# Digital_Isolation.net
KiCad netlist of a schematic drawn in Altium Designer
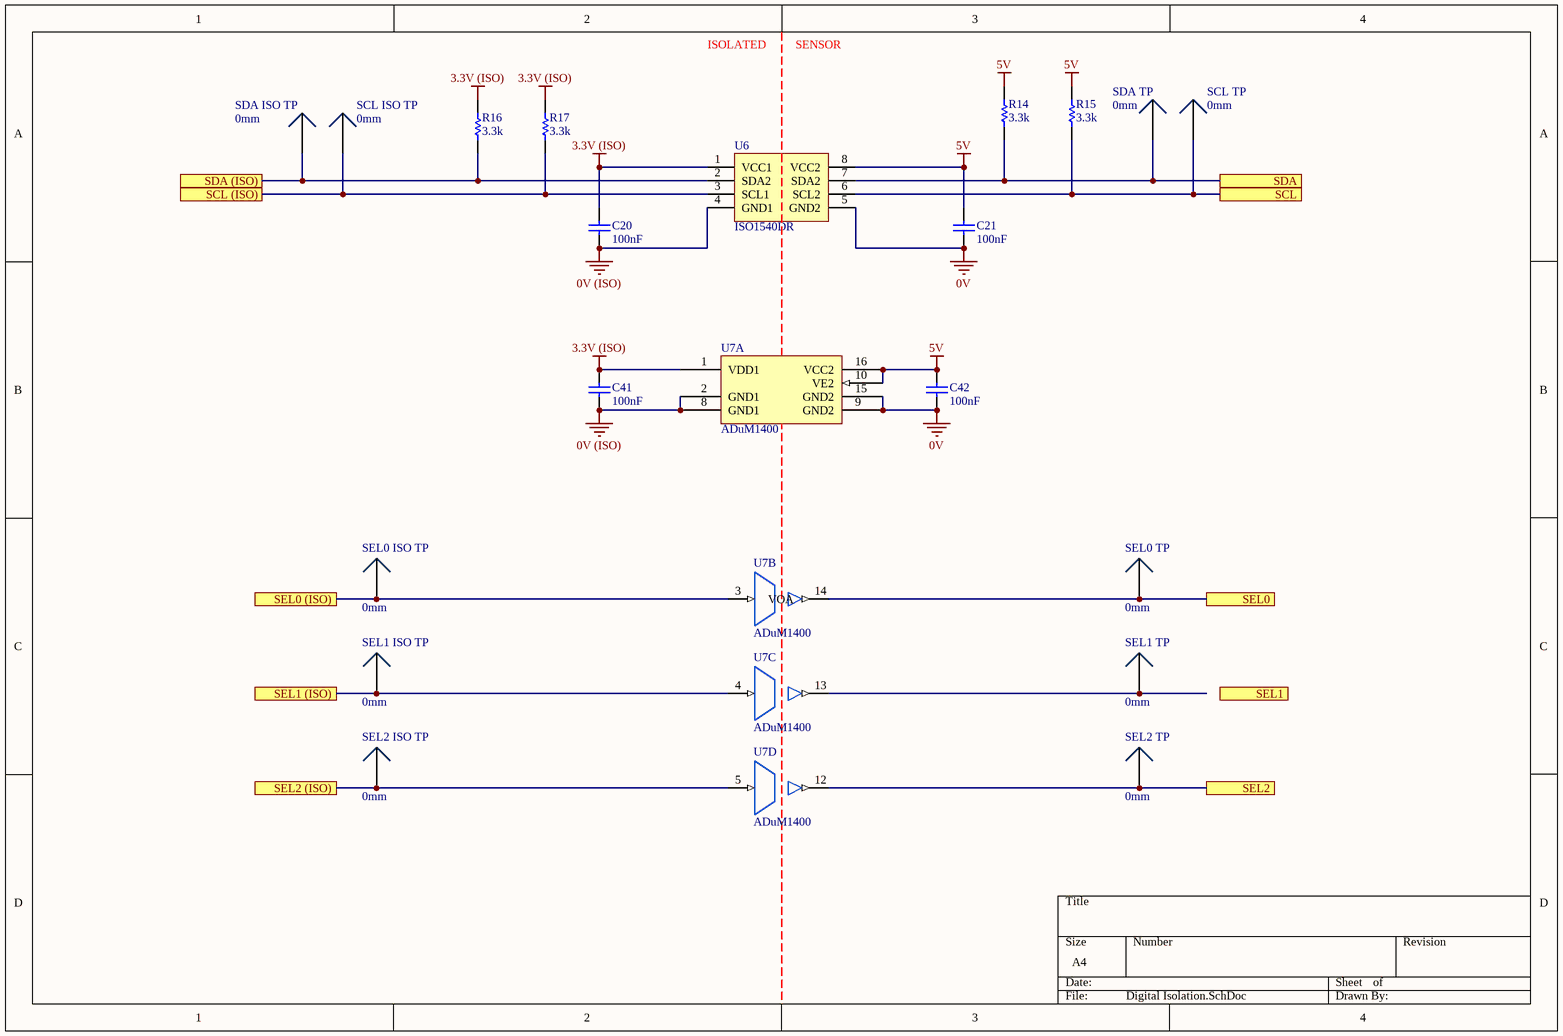
[diagram p0: Digital Isolation.SchDoc]

(export (version "E")
  (design (tool "Eeschema 10.0.6"))
  (components
    (comp (ref "C20")
      (value "100nF")
      (footprint "0805")
      (fields
        (field (name "PART NUMBER") "GCM21BR71E104KA37L")
        (field (name "TOLERANCE") "10%")
        (field (name "MANUFACTURER") "muRata")
      )
      (libsource (lib "ts_20-standard-library") (part "Capacitor"))
    )
    (comp (ref "C21")
      (value "100nF")
      (footprint "0805")
      (fields
        (field (name "PART NUMBER") "GCM21BR71E104KA37L")
        (field (name "TOLERANCE") "10%")
        (field (name "MANUFACTURER") "muRata")
      )
      (libsource (lib "ts_20-standard-library") (part "Capacitor"))
    )
    (comp (ref "C41")
      (value "100nF")
      (footprint "0805")
      (fields
        (field (name "PART NUMBER") "GCM21BR71H104KA37L")
        (field (name "TOLERANCE") "±10%")
        (field (name "MANUFACTURER") "muRata")
      )
      (libsource (lib "ts_20-standard-library") (part "Capacitor"))
    )
    (comp (ref "C42")
      (value "100nF")
      (footprint "0805")
      (fields
        (field (name "PART NUMBER") "GCM21BR71H104KA37L")
        (field (name "TOLERANCE") "±10%")
        (field (name "MANUFACTURER") "muRata")
      )
      (libsource (lib "ts_20-standard-library") (part "Capacitor"))
    )
    (comp (ref "R14")
      (value "3.3k")
      (footprint "0805")
      (fields
        (field (name "PART NUMBER") "RC0805FR073K3L")
        (field (name "MANUFACTURER") "YAGEO")
        (field (name "TOLERANCE") "0.01")
      )
      (libsource (lib "ts_20-standard-library") (part "Resistor"))
    )
    (comp (ref "R15")
      (value "3.3k")
      (footprint "0805")
      (fields
        (field (name "PART NUMBER") "RC0805FR073K3L")
        (field (name "MANUFACTURER") "YAGEO")
        (field (name "TOLERANCE") "0.01")
      )
      (libsource (lib "ts_20-standard-library") (part "Resistor"))
    )
    (comp (ref "R16")
      (value "3.3k")
      (footprint "0805")
      (fields
        (field (name "PART NUMBER") "RC0805FR073K3L")
        (field (name "MANUFACTURER") "YAGEO")
        (field (name "TOLERANCE") "0.01")
      )
      (libsource (lib "ts_20-standard-library") (part "Resistor"))
    )
    (comp (ref "R17")
      (value "3.3k")
      (footprint "0805")
      (fields
        (field (name "PART NUMBER") "RC0805FR073K3L")
        (field (name "MANUFACTURER") "YAGEO")
        (field (name "TOLERANCE") "0.01")
      )
      (libsource (lib "ts_20-standard-library") (part "Resistor"))
    )
    (comp (ref "SCL ISO TP")
      (value "0mm")
      (footprint "SMD Test Point")
      (fields (field (name "PART NUMBER") "SMD Test Point") (field (name "CONTACT") "NA"))
      (libsource (lib "ts_20-standard-connectors") (part "Test Point"))
    )
    (comp (ref "SCL TP")
      (value "0mm")
      (footprint "SMD Test Point")
      (fields (field (name "PART NUMBER") "SMD Test Point") (field (name "CONTACT") "NA"))
      (libsource (lib "ts_20-standard-connectors") (part "Test Point"))
    )
    (comp (ref "SDA ISO TP")
      (value "0mm")
      (footprint "SMD Test Point")
      (fields (field (name "PART NUMBER") "SMD Test Point") (field (name "CONTACT") "NA"))
      (libsource (lib "ts_20-standard-connectors") (part "Test Point"))
    )
    (comp (ref "SDA TP")
      (value "0mm")
      (footprint "SMD Test Point")
      (fields (field (name "PART NUMBER") "SMD Test Point") (field (name "CONTACT") "NA"))
      (libsource (lib "ts_20-standard-connectors") (part "Test Point"))
    )
    (comp (ref "SEL0 ISO TP")
      (value "0mm")
      (footprint "SMD Test Point")
      (fields (field (name "PART NUMBER") "SMD Test Point") (field (name "CONTACT") "NA"))
      (libsource (lib "ts_20-standard-connectors") (part "Test Point"))
    )
    (comp (ref "SEL0 TP")
      (value "0mm")
      (footprint "SMD Test Point")
      (fields (field (name "PART NUMBER") "SMD Test Point") (field (name "CONTACT") "NA"))
      (libsource (lib "ts_20-standard-connectors") (part "Test Point"))
    )
    (comp (ref "SEL1 ISO TP")
      (value "0mm")
      (footprint "SMD Test Point")
      (fields (field (name "PART NUMBER") "SMD Test Point") (field (name "CONTACT") "NA"))
      (libsource (lib "ts_20-standard-connectors") (part "Test Point"))
    )
    (comp (ref "SEL1 TP")
      (value "0mm")
      (footprint "SMD Test Point")
      (fields (field (name "PART NUMBER") "SMD Test Point") (field (name "CONTACT") "NA"))
      (libsource (lib "ts_20-standard-connectors") (part "Test Point"))
    )
    (comp (ref "SEL2 ISO TP")
      (value "0mm")
      (footprint "SMD Test Point")
      (fields (field (name "PART NUMBER") "SMD Test Point") (field (name "CONTACT") "NA"))
      (libsource (lib "ts_20-standard-connectors") (part "Test Point"))
    )
    (comp (ref "SEL2 TP")
      (value "0mm")
      (footprint "SMD Test Point")
      (fields (field (name "PART NUMBER") "SMD Test Point") (field (name "CONTACT") "NA"))
      (libsource (lib "ts_20-standard-connectors") (part "Test Point"))
    )
    (comp (ref "U6")
      (value "ISO1540DR")
      (footprint "TI 8-SOIC")
      (description "I2C Digital Isolator (Multichannel)")
      (fields
        (field (name "MANUFACTURER") "Texas Instruments")
        (field (name "DIGIKEY PART NUMBER") "296-34871-1-ND")
      )
      (libsource (lib "ts_20-standard-library") (part "ISO1540DR"))
    )
    (comp (ref "U7")
      (value "ADuM1400")
      (footprint "AD 16-SOIC")
      (fields
        (field (name "MANUFACTURER") "Analog Devices")
        (field (name "DIGIKEY PART NUMBER") "ADUM1400WSRWZ-ND")
      )
      (libsource (lib "ts_20-standard-library") (part "ADuM1400"))
    )
  )
  (nets
    (net (code "1") (name "/SCL") (class "Default")
      (node (ref "R15") (pin "1") (pinfunction "1_1") (pintype "passive"))
      (node (ref "SCL TP") (pin "1") (pinfunction "1_1") (pintype "passive"))
      (node (ref "U6") (pin "6") (pinfunction "SCL2_6") (pintype "power_in"))
    )
    (net (code "2") (name "/SCL (ISO)") (class "Default")
      (node (ref "R17") (pin "1") (pinfunction "1_1") (pintype "passive"))
      (node (ref "SCL ISO TP") (pin "1") (pinfunction "1_1") (pintype "passive"))
      (node (ref "U6") (pin "3") (pinfunction "SCL1_3") (pintype "power_in"))
    )
    (net (code "3") (name "/SDA") (class "Default")
      (node (ref "R14") (pin "1") (pinfunction "1_1") (pintype "passive"))
      (node (ref "SDA TP") (pin "1") (pinfunction "1_1") (pintype "passive"))
      (node (ref "U6") (pin "7") (pinfunction "SDA2_7") (pintype "power_in"))
    )
    (net (code "4") (name "/SDA (ISO)") (class "Default")
      (node (ref "R16") (pin "1") (pinfunction "1_1") (pintype "passive"))
      (node (ref "SDA ISO TP") (pin "1") (pinfunction "1_1") (pintype "passive"))
      (node (ref "U6") (pin "2") (pinfunction "SDA2_2") (pintype "power_in"))
    )
    (net (code "5") (name "/SEL0") (class "Default")
      (node (ref "SEL0 TP") (pin "1") (pinfunction "1_1") (pintype "passive"))
      (node (ref "U7") (pin "14") (pinfunction "VOA_14") (pintype "output"))
    )
    (net (code "6") (name "/SEL0 (ISO)") (class "Default")
      (node (ref "SEL0 ISO TP") (pin "1") (pinfunction "1_1") (pintype "passive"))
      (node (ref "U7") (pin "3") (pinfunction "VIA_3") (pintype "input"))
    )
    (net (code "8") (name "/SEL1 (ISO)") (class "Default")
      (node (ref "SEL1 ISO TP") (pin "1") (pinfunction "1_1") (pintype "passive"))
      (node (ref "U7") (pin "4") (pinfunction "VIB_4") (pintype "input"))
    )
    (net (code "9") (name "/SEL2") (class "Default")
      (node (ref "SEL2 TP") (pin "1") (pinfunction "1_1") (pintype "passive"))
      (node (ref "U7") (pin "12") (pinfunction "VOC_12") (pintype "output"))
    )
    (net (code "10") (name "/SEL2 (ISO)") (class "Default")
      (node (ref "SEL2 ISO TP") (pin "1") (pinfunction "1_1") (pintype "passive"))
      (node (ref "U7") (pin "5") (pinfunction "VIC_5") (pintype "input"))
    )
    (net (code "11") (name "0V") (class "Default")
      (node (ref "C21") (pin "1") (pinfunction "1_1") (pintype "passive"))
      (node (ref "C42") (pin "1") (pinfunction "1_1") (pintype "passive"))
      (node (ref "U6") (pin "5") (pinfunction "GND2_5") (pintype "power_in"))
      (node (ref "U7") (pin "15") (pinfunction "GND2_15") (pintype "power_in"))
      (node (ref "U7") (pin "9") (pinfunction "GND2_9") (pintype "power_in"))
    )
    (net (code "12") (name "0V (ISO)") (class "Default")
      (node (ref "C20") (pin "1") (pinfunction "1_1") (pintype "passive"))
      (node (ref "C41") (pin "1") (pinfunction "1_1") (pintype "passive"))
      (node (ref "U6") (pin "4") (pinfunction "GND1_4") (pintype "power_in"))
      (node (ref "U7") (pin "2") (pinfunction "GND1_2") (pintype "power_in"))
      (node (ref "U7") (pin "8") (pinfunction "GND1_8") (pintype "power_in"))
    )
    (net (code "13") (name "3.3V (ISO)") (class "Default")
      (node (ref "C20") (pin "2") (pinfunction "2_2") (pintype "passive"))
      (node (ref "C41") (pin "2") (pinfunction "2_2") (pintype "passive"))
      (node (ref "R16") (pin "2") (pinfunction "2_2") (pintype "passive"))
      (node (ref "R17") (pin "2") (pinfunction "2_2") (pintype "passive"))
      (node (ref "U6") (pin "1") (pinfunction "VCC1_1") (pintype "power_in"))
      (node (ref "U7") (pin "1") (pinfunction "VDD1_1") (pintype "power_in"))
    )
    (net (code "14") (name "5V") (class "Default")
      (node (ref "C21") (pin "2") (pinfunction "2_2") (pintype "passive"))
      (node (ref "C42") (pin "2") (pinfunction "2_2") (pintype "passive"))
      (node (ref "R14") (pin "2") (pinfunction "2_2") (pintype "passive"))
      (node (ref "R15") (pin "2") (pinfunction "2_2") (pintype "passive"))
      (node (ref "U6") (pin "8") (pinfunction "VCC2_8") (pintype "power_in"))
      (node (ref "U7") (pin "10") (pinfunction "VE2_10") (pintype "input"))
      (node (ref "U7") (pin "16") (pinfunction "VCC2_16") (pintype "power_in"))
    )
    (net (code "15") (name "Net-(U7C-VOB)") (class "Default")
      (node (ref "SEL1 TP") (pin "1") (pinfunction "1_1") (pintype "passive"))
      (node (ref "U7") (pin "13") (pinfunction "VOB_13") (pintype "output"))
    )
  )
)
